# Netscale48HD_Antenna_Selector.net
KiCad netlist of a schematic drawn in Altium Designer
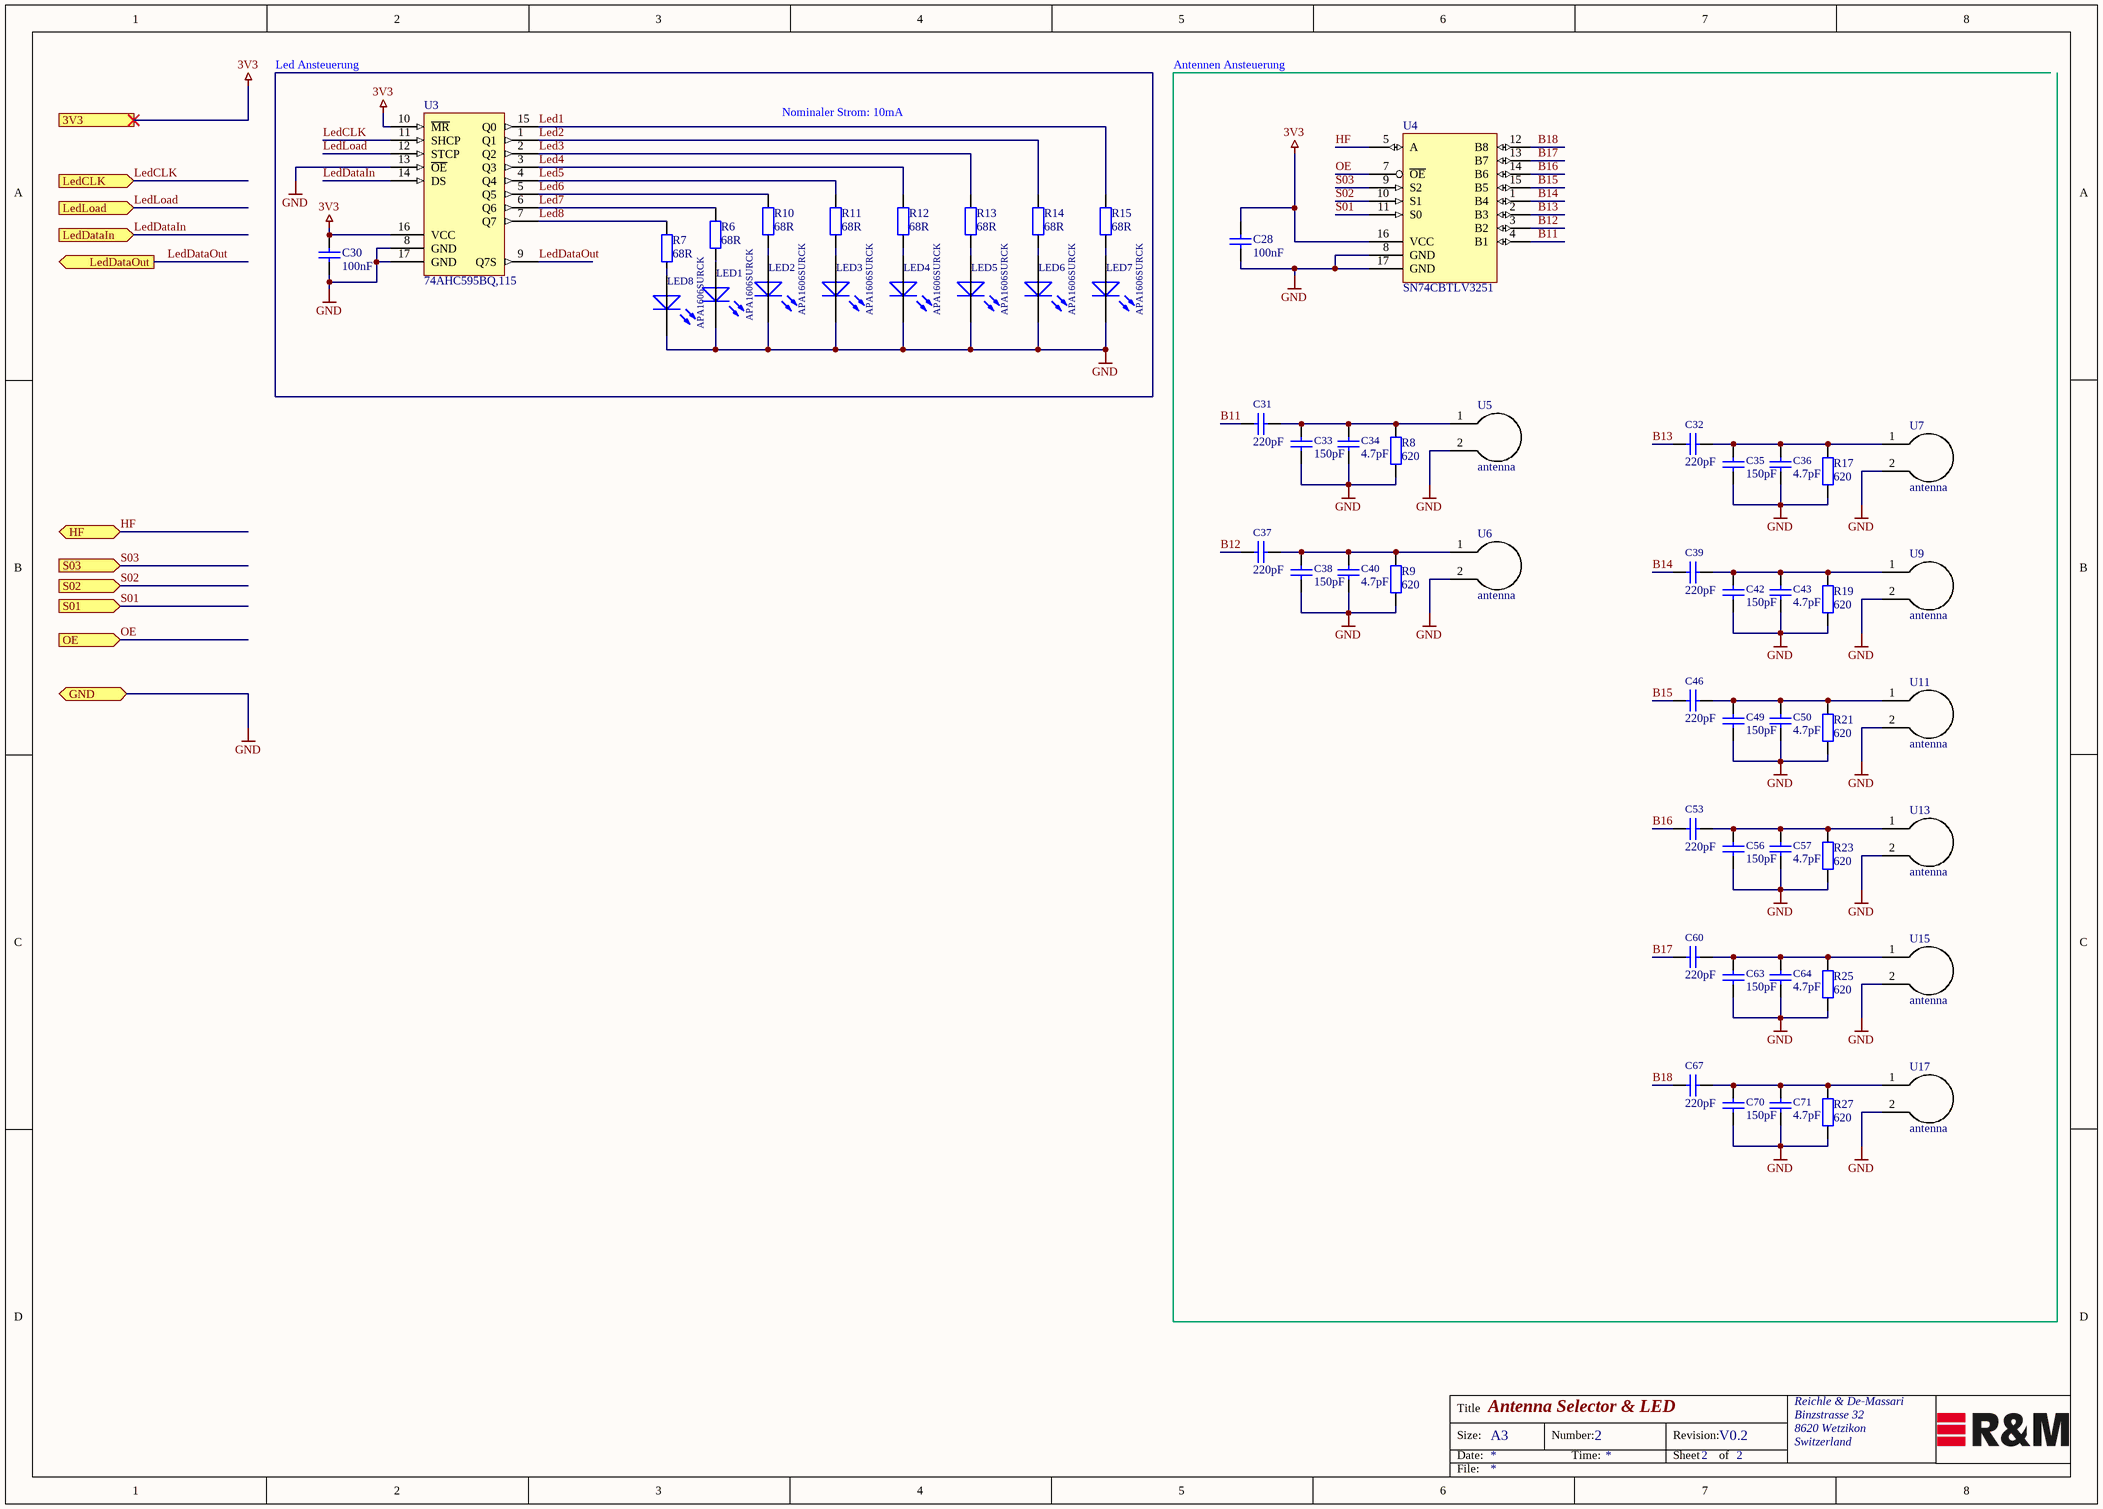
[diagram p0: Netscale48HD_Antenna_Selector.SchDoc]

(export (version "E")
  (design (tool "Eeschema 10.0.6"))
  (components
    (comp (ref "C28")
      (value "100nF")
      (footprint "CAPC1005X55N")
      (description "0.1µF ±10% 10V Ceramic Capacitor X5R 0402 (1005 Metric)")
      (fields (field (name "TOLERANCE") "Â±10%") (field (name "MANUFACTURER") "Taiyo Yuden"))
      (libsource (lib "altium-import") (part "root_1_CMP-1033-00660-1_"))
    )
    (comp (ref "C30")
      (value "100nF")
      (footprint "CAPC1005X55N")
      (description "0.1µF ±10% 10V Ceramic Capacitor X5R 0402 (1005 Metric)")
      (fields (field (name "TOLERANCE") "Â±10%") (field (name "MANUFACTURER") "Taiyo Yuden"))
      (libsource (lib "altium-import") (part "root_1_CMP-1033-00660-1_"))
    )
    (comp (ref "C31")
      (value "220pF")
      (footprint "CAPC1005X55N")
      (description "220pF ±1% 50V Ceramic Capacitor C0G, NP0 0402 (1005 Metric)")
      (fields
        (field (name "MANUFACTURER") "Murata Electronics")
        (field (name "Comment") "GCM1555C1H221FA16D")
      )
      (libsource (lib "NTB Vault") (part "706xx_R+M_InteliPhyII_KTI-00070-A.1"))
    )
    (comp (ref "C32")
      (value "220pF")
      (footprint "CAPC1005X55N")
      (description "220pF ±1% 50V Ceramic Capacitor C0G, NP0 0402 (1005 Metric)")
      (fields
        (field (name "MANUFACTURER") "Murata Electronics")
        (field (name "Comment") "GCM1555C1H221FA16D")
      )
      (libsource (lib "NTB Vault") (part "706xx_R+M_InteliPhyII_KTI-00070-A.1"))
    )
    (comp (ref "C33")
      (value "150pF")
      (footprint "CAPC1005X55N")
      (description "150pF ±1% 50V Ceramic Capacitor C0G, NP0 0402 (1005 Metric)")
      (fields
        (field (name "MANUFACTURER") "Murata Electronics North America")
        (field (name "Comment") "GRM1555C1H151FA01D")
      )
      (libsource (lib "NTB Vault") (part "706xx_R+M_InteliPhyII_KTI-00069-A.1"))
    )
    (comp (ref "C34")
      (value "4.7pF")
      (footprint "CAPC1005X55N")
      (description "4.7pF ±0.05pF 50V Ceramic Capacitor C0G, NP0 0402 (1005 Metric)")
      (fields
        (field (name "MANUFACTURER") "Murata Electronics North America")
        (field (name "Comment") "GJM1555C1H4R7WB01D")
      )
      (libsource (lib "NTB Vault") (part "706xx_R+M_InteliPhyII_KTI-00023-A.1"))
    )
    (comp (ref "C35")
      (value "150pF")
      (footprint "CAPC1005X55N")
      (description "150pF ±1% 50V Ceramic Capacitor C0G, NP0 0402 (1005 Metric)")
      (fields
        (field (name "MANUFACTURER") "Murata Electronics North America")
        (field (name "Comment") "GRM1555C1H151FA01D")
      )
      (libsource (lib "NTB Vault") (part "706xx_R+M_InteliPhyII_KTI-00069-A.1"))
    )
    (comp (ref "C36")
      (value "4.7pF")
      (footprint "CAPC1005X55N")
      (description "4.7pF ±0.05pF 50V Ceramic Capacitor C0G, NP0 0402 (1005 Metric)")
      (fields
        (field (name "MANUFACTURER") "Murata Electronics North America")
        (field (name "Comment") "GJM1555C1H4R7WB01D")
      )
      (libsource (lib "NTB Vault") (part "706xx_R+M_InteliPhyII_KTI-00023-A.1"))
    )
    (comp (ref "C37")
      (value "220pF")
      (footprint "CAPC1005X55N")
      (description "220pF ±1% 50V Ceramic Capacitor C0G, NP0 0402 (1005 Metric)")
      (fields
        (field (name "MANUFACTURER") "Murata Electronics")
        (field (name "Comment") "GCM1555C1H221FA16D")
      )
      (libsource (lib "NTB Vault") (part "706xx_R+M_InteliPhyII_KTI-00070-A.1"))
    )
    (comp (ref "C38")
      (value "150pF")
      (footprint "CAPC1005X55N")
      (description "150pF ±1% 50V Ceramic Capacitor C0G, NP0 0402 (1005 Metric)")
      (fields
        (field (name "MANUFACTURER") "Murata Electronics North America")
        (field (name "Comment") "GRM1555C1H151FA01D")
      )
      (libsource (lib "NTB Vault") (part "706xx_R+M_InteliPhyII_KTI-00069-A.1"))
    )
    (comp (ref "C39")
      (value "220pF")
      (footprint "CAPC1005X55N")
      (description "220pF ±1% 50V Ceramic Capacitor C0G, NP0 0402 (1005 Metric)")
      (fields
        (field (name "MANUFACTURER") "Murata Electronics")
        (field (name "Comment") "GCM1555C1H221FA16D")
      )
      (libsource (lib "NTB Vault") (part "706xx_R+M_InteliPhyII_KTI-00070-A.1"))
    )
    (comp (ref "C40")
      (value "4.7pF")
      (footprint "CAPC1005X55N")
      (description "4.7pF ±0.05pF 50V Ceramic Capacitor C0G, NP0 0402 (1005 Metric)")
      (fields
        (field (name "MANUFACTURER") "Murata Electronics North America")
        (field (name "Comment") "GJM1555C1H4R7WB01D")
      )
      (libsource (lib "NTB Vault") (part "706xx_R+M_InteliPhyII_KTI-00023-A.1"))
    )
    (comp (ref "C42")
      (value "150pF")
      (footprint "CAPC1005X55N")
      (description "150pF ±1% 50V Ceramic Capacitor C0G, NP0 0402 (1005 Metric)")
      (fields
        (field (name "MANUFACTURER") "Murata Electronics North America")
        (field (name "Comment") "GRM1555C1H151FA01D")
      )
      (libsource (lib "NTB Vault") (part "706xx_R+M_InteliPhyII_KTI-00069-A.1"))
    )
    (comp (ref "C43")
      (value "4.7pF")
      (footprint "CAPC1005X55N")
      (description "4.7pF ±0.05pF 50V Ceramic Capacitor C0G, NP0 0402 (1005 Metric)")
      (fields
        (field (name "MANUFACTURER") "Murata Electronics North America")
        (field (name "Comment") "GJM1555C1H4R7WB01D")
      )
      (libsource (lib "NTB Vault") (part "706xx_R+M_InteliPhyII_KTI-00023-A.1"))
    )
    (comp (ref "C46")
      (value "220pF")
      (footprint "CAPC1005X55N")
      (description "220pF ±1% 50V Ceramic Capacitor C0G, NP0 0402 (1005 Metric)")
      (fields
        (field (name "MANUFACTURER") "Murata Electronics")
        (field (name "Comment") "GCM1555C1H221FA16D")
      )
      (libsource (lib "NTB Vault") (part "706xx_R+M_InteliPhyII_KTI-00070-A.1"))
    )
    (comp (ref "C49")
      (value "150pF")
      (footprint "CAPC1005X55N")
      (description "150pF ±1% 50V Ceramic Capacitor C0G, NP0 0402 (1005 Metric)")
      (fields
        (field (name "MANUFACTURER") "Murata Electronics North America")
        (field (name "Comment") "GRM1555C1H151FA01D")
      )
      (libsource (lib "NTB Vault") (part "706xx_R+M_InteliPhyII_KTI-00069-A.1"))
    )
    (comp (ref "C50")
      (value "4.7pF")
      (footprint "CAPC1005X55N")
      (description "4.7pF ±0.05pF 50V Ceramic Capacitor C0G, NP0 0402 (1005 Metric)")
      (fields
        (field (name "MANUFACTURER") "Murata Electronics North America")
        (field (name "Comment") "GJM1555C1H4R7WB01D")
      )
      (libsource (lib "NTB Vault") (part "706xx_R+M_InteliPhyII_KTI-00023-A.1"))
    )
    (comp (ref "C53")
      (value "220pF")
      (footprint "CAPC1005X55N")
      (description "220pF ±1% 50V Ceramic Capacitor C0G, NP0 0402 (1005 Metric)")
      (fields
        (field (name "MANUFACTURER") "Murata Electronics")
        (field (name "Comment") "GCM1555C1H221FA16D")
      )
      (libsource (lib "NTB Vault") (part "706xx_R+M_InteliPhyII_KTI-00070-A.1"))
    )
    (comp (ref "C56")
      (value "150pF")
      (footprint "CAPC1005X55N")
      (description "150pF ±1% 50V Ceramic Capacitor C0G, NP0 0402 (1005 Metric)")
      (fields
        (field (name "MANUFACTURER") "Murata Electronics North America")
        (field (name "Comment") "GRM1555C1H151FA01D")
      )
      (libsource (lib "NTB Vault") (part "706xx_R+M_InteliPhyII_KTI-00069-A.1"))
    )
    (comp (ref "C57")
      (value "4.7pF")
      (footprint "CAPC1005X55N")
      (description "4.7pF ±0.05pF 50V Ceramic Capacitor C0G, NP0 0402 (1005 Metric)")
      (fields
        (field (name "MANUFACTURER") "Murata Electronics North America")
        (field (name "Comment") "GJM1555C1H4R7WB01D")
      )
      (libsource (lib "NTB Vault") (part "706xx_R+M_InteliPhyII_KTI-00023-A.1"))
    )
    (comp (ref "C60")
      (value "220pF")
      (footprint "CAPC1005X55N")
      (description "220pF ±1% 50V Ceramic Capacitor C0G, NP0 0402 (1005 Metric)")
      (fields
        (field (name "MANUFACTURER") "Murata Electronics")
        (field (name "Comment") "GCM1555C1H221FA16D")
      )
      (libsource (lib "NTB Vault") (part "706xx_R+M_InteliPhyII_KTI-00070-A.1"))
    )
    (comp (ref "C63")
      (value "150pF")
      (footprint "CAPC1005X55N")
      (description "150pF ±1% 50V Ceramic Capacitor C0G, NP0 0402 (1005 Metric)")
      (fields
        (field (name "MANUFACTURER") "Murata Electronics North America")
        (field (name "Comment") "GRM1555C1H151FA01D")
      )
      (libsource (lib "NTB Vault") (part "706xx_R+M_InteliPhyII_KTI-00069-A.1"))
    )
    (comp (ref "C64")
      (value "4.7pF")
      (footprint "CAPC1005X55N")
      (description "4.7pF ±0.05pF 50V Ceramic Capacitor C0G, NP0 0402 (1005 Metric)")
      (fields
        (field (name "MANUFACTURER") "Murata Electronics North America")
        (field (name "Comment") "GJM1555C1H4R7WB01D")
      )
      (libsource (lib "NTB Vault") (part "706xx_R+M_InteliPhyII_KTI-00023-A.1"))
    )
    (comp (ref "C67")
      (value "220pF")
      (footprint "CAPC1005X55N")
      (description "220pF ±1% 50V Ceramic Capacitor C0G, NP0 0402 (1005 Metric)")
      (fields
        (field (name "MANUFACTURER") "Murata Electronics")
        (field (name "Comment") "GCM1555C1H221FA16D")
      )
      (libsource (lib "NTB Vault") (part "706xx_R+M_InteliPhyII_KTI-00070-A.1"))
    )
    (comp (ref "C70")
      (value "150pF")
      (footprint "CAPC1005X55N")
      (description "150pF ±1% 50V Ceramic Capacitor C0G, NP0 0402 (1005 Metric)")
      (fields
        (field (name "MANUFACTURER") "Murata Electronics North America")
        (field (name "Comment") "GRM1555C1H151FA01D")
      )
      (libsource (lib "NTB Vault") (part "706xx_R+M_InteliPhyII_KTI-00069-A.1"))
    )
    (comp (ref "C71")
      (value "4.7pF")
      (footprint "CAPC1005X55N")
      (description "4.7pF ±0.05pF 50V Ceramic Capacitor C0G, NP0 0402 (1005 Metric)")
      (fields
        (field (name "MANUFACTURER") "Murata Electronics North America")
        (field (name "Comment") "GJM1555C1H4R7WB01D")
      )
      (libsource (lib "NTB Vault") (part "706xx_R+M_InteliPhyII_KTI-00023-A.1"))
    )
    (comp (ref "LED1")
      (value "APA1606SURCK")
      (footprint "Kingbright_SMD_2_RWH")
      (description "Red 630nm LED Indication - Discrete 1.95V 2-SMD, No Lead")
      (fields (field (name "MANUFACTURER") "Kingbright"))
      (libsource (lib "altium-import") (part "root_1_LED_K1_A2_"))
    )
    (comp (ref "LED2")
      (value "APA1606SURCK")
      (footprint "Kingbright_SMD_2_RWH")
      (description "Red 630nm LED Indication - Discrete 1.95V 2-SMD, No Lead")
      (fields (field (name "MANUFACTURER") "Kingbright"))
      (libsource (lib "altium-import") (part "root_1_LED_K1_A2_"))
    )
    (comp (ref "LED3")
      (value "APA1606SURCK")
      (footprint "Kingbright_SMD_2_RWH")
      (description "Red 630nm LED Indication - Discrete 1.95V 2-SMD, No Lead")
      (fields (field (name "MANUFACTURER") "Kingbright"))
      (libsource (lib "altium-import") (part "root_1_LED_K1_A2_"))
    )
    (comp (ref "LED4")
      (value "APA1606SURCK")
      (footprint "Kingbright_SMD_2_RWH")
      (description "Red 630nm LED Indication - Discrete 1.95V 2-SMD, No Lead")
      (fields (field (name "MANUFACTURER") "Kingbright"))
      (libsource (lib "altium-import") (part "root_1_LED_K1_A2_"))
    )
    (comp (ref "LED5")
      (value "APA1606SURCK")
      (footprint "Kingbright_SMD_2_RWH")
      (description "Red 630nm LED Indication - Discrete 1.95V 2-SMD, No Lead")
      (fields (field (name "MANUFACTURER") "Kingbright"))
      (libsource (lib "altium-import") (part "root_1_LED_K1_A2_"))
    )
    (comp (ref "LED6")
      (value "APA1606SURCK")
      (footprint "Kingbright_SMD_2_RWH")
      (description "Red 630nm LED Indication - Discrete 1.95V 2-SMD, No Lead")
      (fields (field (name "MANUFACTURER") "Kingbright"))
      (libsource (lib "altium-import") (part "root_1_LED_K1_A2_"))
    )
    (comp (ref "LED7")
      (value "APA1606SURCK")
      (footprint "Kingbright_SMD_2_RWH")
      (description "Red 630nm LED Indication - Discrete 1.95V 2-SMD, No Lead")
      (fields (field (name "MANUFACTURER") "Kingbright"))
      (libsource (lib "altium-import") (part "root_1_LED_K1_A2_"))
    )
    (comp (ref "LED8")
      (value "APA1606SURCK")
      (footprint "Kingbright_SMD_2_RWH")
      (description "Red 630nm LED Indication - Discrete 1.95V 2-SMD, No Lead")
      (fields (field (name "MANUFACTURER") "Kingbright"))
      (libsource (lib "altium-import") (part "root_1_LED_K1_A2_"))
    )
    (comp (ref "R6")
      (value "68R")
      (footprint "RESC1005X40N")
      (description "68 Ohms ±1% 0.125W, 1/8W Chip Resistor 0402 (1005 Metric) Pulse Withstanding Thick Film")
      (fields
        (field (name "MANUFACTURER") "TE Connectivity Passive Product")
        (field (name "Comment") "CRGP0402F68R")
      )
      (libsource (lib "RDM_Altium_Library") (part "PassResBas0201-00055-A.2"))
    )
    (comp (ref "R7")
      (value "68R")
      (footprint "RESC1005X40N")
      (description "68 Ohms ±1% 0.125W, 1/8W Chip Resistor 0402 (1005 Metric) Pulse Withstanding Thick Film")
      (fields
        (field (name "MANUFACTURER") "TE Connectivity Passive Product")
        (field (name "Comment") "CRGP0402F68R")
      )
      (libsource (lib "RDM_Altium_Library") (part "PassResBas0201-00055-A.2"))
    )
    (comp (ref "R8")
      (value "620")
      (footprint "RESC1005X40N")
      (description "620 Ohms ±1% 0.1W, 1/10W Chip Resistor 0402 (1005 Metric) Automotive AEC-Q200 Thick Film")
      (fields
        (field (name "MANUFACTURER") "Panasonic Electronic Components")
        (field (name "Comment") "ERJ-2RKF6200X")
      )
      (libsource (lib "") (part "PassResBas0201-00055-A.2_1"))
    )
    (comp (ref "R9")
      (value "620")
      (footprint "RESC1005X40N")
      (description "620 Ohms ±1% 0.1W, 1/10W Chip Resistor 0402 (1005 Metric) Automotive AEC-Q200 Thick Film")
      (fields
        (field (name "MANUFACTURER") "Panasonic Electronic Components")
        (field (name "Comment") "ERJ-2RKF6200X")
      )
      (libsource (lib "") (part "PassResBas0201-00055-A.2_1"))
    )
    (comp (ref "R10")
      (value "68R")
      (footprint "RESC1005X40N")
      (description "68 Ohms ±1% 0.125W, 1/8W Chip Resistor 0402 (1005 Metric) Pulse Withstanding Thick Film")
      (fields
        (field (name "MANUFACTURER") "TE Connectivity Passive Product")
        (field (name "Comment") "CRGP0402F68R")
      )
      (libsource (lib "RDM_Altium_Library") (part "PassResBas0201-00055-A.2"))
    )
    (comp (ref "R11")
      (value "68R")
      (footprint "RESC1005X40N")
      (description "68 Ohms ±1% 0.125W, 1/8W Chip Resistor 0402 (1005 Metric) Pulse Withstanding Thick Film")
      (fields
        (field (name "MANUFACTURER") "TE Connectivity Passive Product")
        (field (name "Comment") "CRGP0402F68R")
      )
      (libsource (lib "RDM_Altium_Library") (part "PassResBas0201-00055-A.2"))
    )
    (comp (ref "R12")
      (value "68R")
      (footprint "RESC1005X40N")
      (description "68 Ohms ±1% 0.125W, 1/8W Chip Resistor 0402 (1005 Metric) Pulse Withstanding Thick Film")
      (fields
        (field (name "MANUFACTURER") "TE Connectivity Passive Product")
        (field (name "Comment") "CRGP0402F68R")
      )
      (libsource (lib "RDM_Altium_Library") (part "PassResBas0201-00055-A.2"))
    )
    (comp (ref "R13")
      (value "68R")
      (footprint "RESC1005X40N")
      (description "68 Ohms ±1% 0.125W, 1/8W Chip Resistor 0402 (1005 Metric) Pulse Withstanding Thick Film")
      (fields
        (field (name "MANUFACTURER") "TE Connectivity Passive Product")
        (field (name "Comment") "CRGP0402F68R")
      )
      (libsource (lib "RDM_Altium_Library") (part "PassResBas0201-00055-A.2"))
    )
    (comp (ref "R14")
      (value "68R")
      (footprint "RESC1005X40N")
      (description "68 Ohms ±1% 0.125W, 1/8W Chip Resistor 0402 (1005 Metric) Pulse Withstanding Thick Film")
      (fields
        (field (name "MANUFACTURER") "TE Connectivity Passive Product")
        (field (name "Comment") "CRGP0402F68R")
      )
      (libsource (lib "RDM_Altium_Library") (part "PassResBas0201-00055-A.2"))
    )
    (comp (ref "R15")
      (value "68R")
      (footprint "RESC1005X40N")
      (description "68 Ohms ±1% 0.125W, 1/8W Chip Resistor 0402 (1005 Metric) Pulse Withstanding Thick Film")
      (fields
        (field (name "MANUFACTURER") "TE Connectivity Passive Product")
        (field (name "Comment") "CRGP0402F68R")
      )
      (libsource (lib "RDM_Altium_Library") (part "PassResBas0201-00055-A.2"))
    )
    (comp (ref "R17")
      (value "620")
      (footprint "RESC1005X40N")
      (description "620 Ohms ±1% 0.1W, 1/10W Chip Resistor 0402 (1005 Metric) Automotive AEC-Q200 Thick Film")
      (fields
        (field (name "MANUFACTURER") "Panasonic Electronic Components")
        (field (name "Comment") "ERJ-2RKF6200X")
      )
      (libsource (lib "") (part "PassResBas0201-00055-A.2_1"))
    )
    (comp (ref "R19")
      (value "620")
      (footprint "RESC1005X40N")
      (description "620 Ohms ±1% 0.1W, 1/10W Chip Resistor 0402 (1005 Metric) Automotive AEC-Q200 Thick Film")
      (fields
        (field (name "MANUFACTURER") "Panasonic Electronic Components")
        (field (name "Comment") "ERJ-2RKF6200X")
      )
      (libsource (lib "") (part "PassResBas0201-00055-A.2_1"))
    )
    (comp (ref "R21")
      (value "620")
      (footprint "RESC1005X40N")
      (description "620 Ohms ±1% 0.1W, 1/10W Chip Resistor 0402 (1005 Metric) Automotive AEC-Q200 Thick Film")
      (fields
        (field (name "MANUFACTURER") "Panasonic Electronic Components")
        (field (name "Comment") "ERJ-2RKF6200X")
      )
      (libsource (lib "") (part "PassResBas0201-00055-A.2_1"))
    )
    (comp (ref "R23")
      (value "620")
      (footprint "RESC1005X40N")
      (description "620 Ohms ±1% 0.1W, 1/10W Chip Resistor 0402 (1005 Metric) Automotive AEC-Q200 Thick Film")
      (fields
        (field (name "MANUFACTURER") "Panasonic Electronic Components")
        (field (name "Comment") "ERJ-2RKF6200X")
      )
      (libsource (lib "") (part "PassResBas0201-00055-A.2_1"))
    )
    (comp (ref "R25")
      (value "620")
      (footprint "RESC1005X40N")
      (description "620 Ohms ±1% 0.1W, 1/10W Chip Resistor 0402 (1005 Metric) Automotive AEC-Q200 Thick Film")
      (fields
        (field (name "MANUFACTURER") "Panasonic Electronic Components")
        (field (name "Comment") "ERJ-2RKF6200X")
      )
      (libsource (lib "") (part "PassResBas0201-00055-A.2_1"))
    )
    (comp (ref "R27")
      (value "620")
      (footprint "RESC1005X40N")
      (description "620 Ohms ±1% 0.1W, 1/10W Chip Resistor 0402 (1005 Metric) Automotive AEC-Q200 Thick Film")
      (fields
        (field (name "MANUFACTURER") "Panasonic Electronic Components")
        (field (name "Comment") "ERJ-2RKF6200X")
      )
      (libsource (lib "") (part "PassResBas0201-00055-A.2_1"))
    )
    (comp (ref "U3")
      (value "74AHC595BQ,115")
      (footprint "NexperiaUSAInc_16-VFQFN_16_R")
      (description "IC 8BIT SHIFT REGISTER 16HVQFN")
      (fields (field (name "MANUFACTURER") "Nexperia USA Inc."))
      (libsource (lib "RDM_Altium_Library") (part "NexperiaUSAInc_74AHC595,115_16-VFQFN_16"))
    )
    (comp (ref "U4")
      (value "SN74CBTLV3251")
      (footprint "TexasInstruments_16-VFQFN_16_R")
      (description "Multiplexer Switch ICs Sngl-Pole Dbl-Throw Analog Switch")
      (fields (field (name "MANUFACTURER") "Texas Instruments"))
      (libsource (lib "RDM_Altium_Library") (part "SN74CBTLV3251RGYR"))
    )
    (comp (ref "U5")
      (value "antenna")
      (footprint "antenna_1_layer")
      (libsource (lib "RDM_Altium_Library") (part "antenna"))
    )
    (comp (ref "U6")
      (value "antenna")
      (footprint "antenna_1_layer")
      (libsource (lib "RDM_Altium_Library") (part "antenna"))
    )
    (comp (ref "U7")
      (value "antenna")
      (footprint "antenna_1_layer")
      (libsource (lib "RDM_Altium_Library") (part "antenna"))
    )
    (comp (ref "U9")
      (value "antenna")
      (footprint "antenna_1_layer")
      (libsource (lib "RDM_Altium_Library") (part "antenna"))
    )
    (comp (ref "U11")
      (value "antenna")
      (footprint "antenna_1_layer")
      (libsource (lib "RDM_Altium_Library") (part "antenna"))
    )
    (comp (ref "U13")
      (value "antenna")
      (footprint "antenna_1_layer")
      (libsource (lib "RDM_Altium_Library") (part "antenna"))
    )
    (comp (ref "U15")
      (value "antenna")
      (footprint "antenna_1_layer")
      (libsource (lib "RDM_Altium_Library") (part "antenna"))
    )
    (comp (ref "U17")
      (value "antenna")
      (footprint "antenna_1_layer")
      (libsource (lib "RDM_Altium_Library") (part "antenna"))
    )
  )
  (nets
    (net (code "1") (name "/B11") (class "Default")
      (node (ref "C31") (pin "1") (pinfunction "Pos_1") (pintype "passive"))
      (node (ref "U4") (pin "4") (pinfunction "B1_4") (pintype "bidirectional"))
    )
    (net (code "2") (name "/B12") (class "Default")
      (node (ref "C37") (pin "1") (pinfunction "Pos_1") (pintype "passive"))
      (node (ref "U4") (pin "3") (pinfunction "B2_3") (pintype "bidirectional"))
    )
    (net (code "3") (name "/B13") (class "Default")
      (node (ref "C32") (pin "1") (pinfunction "Pos_1") (pintype "passive"))
      (node (ref "U4") (pin "2") (pinfunction "B3_2") (pintype "bidirectional"))
    )
    (net (code "4") (name "/B14") (class "Default")
      (node (ref "C39") (pin "1") (pinfunction "Pos_1") (pintype "passive"))
      (node (ref "U4") (pin "1") (pinfunction "B4_1") (pintype "bidirectional"))
    )
    (net (code "5") (name "/B15") (class "Default")
      (node (ref "C46") (pin "1") (pinfunction "Pos_1") (pintype "passive"))
      (node (ref "U4") (pin "15") (pinfunction "B5_15") (pintype "bidirectional"))
    )
    (net (code "6") (name "/B16") (class "Default")
      (node (ref "C53") (pin "1") (pinfunction "Pos_1") (pintype "passive"))
      (node (ref "U4") (pin "14") (pinfunction "B6_14") (pintype "bidirectional"))
    )
    (net (code "7") (name "/B17") (class "Default")
      (node (ref "C60") (pin "1") (pinfunction "Pos_1") (pintype "passive"))
      (node (ref "U4") (pin "13") (pinfunction "B7_13") (pintype "bidirectional"))
    )
    (net (code "8") (name "/B18") (class "Default")
      (node (ref "C67") (pin "1") (pinfunction "Pos_1") (pintype "passive"))
      (node (ref "U4") (pin "12") (pinfunction "B8_12") (pintype "bidirectional"))
    )
    (net (code "9") (name "/HF") (class "Default")
      (node (ref "U4") (pin "5") (pinfunction "A_5") (pintype "bidirectional"))
    )
    (net (code "10") (name "/Led1") (class "Default")
      (node (ref "R15") (pin "1") (pinfunction "1_1") (pintype "passive"))
      (node (ref "U3") (pin "15") (pinfunction "Q0_15") (pintype "output"))
    )
    (net (code "11") (name "/Led2") (class "Default")
      (node (ref "R14") (pin "1") (pinfunction "1_1") (pintype "passive"))
      (node (ref "U3") (pin "1") (pinfunction "Q1_1") (pintype "output"))
    )
    (net (code "12") (name "/Led3") (class "Default")
      (node (ref "R13") (pin "1") (pinfunction "1_1") (pintype "passive"))
      (node (ref "U3") (pin "2") (pinfunction "Q2_2") (pintype "output"))
    )
    (net (code "13") (name "/Led4") (class "Default")
      (node (ref "R12") (pin "1") (pinfunction "1_1") (pintype "passive"))
      (node (ref "U3") (pin "3") (pinfunction "Q3_3") (pintype "output"))
    )
    (net (code "14") (name "/Led5") (class "Default")
      (node (ref "R11") (pin "1") (pinfunction "1_1") (pintype "passive"))
      (node (ref "U3") (pin "4") (pinfunction "Q4_4") (pintype "output"))
    )
    (net (code "15") (name "/Led6") (class "Default")
      (node (ref "R10") (pin "1") (pinfunction "1_1") (pintype "passive"))
      (node (ref "U3") (pin "5") (pinfunction "Q5_5") (pintype "output"))
    )
    (net (code "16") (name "/Led7") (class "Default")
      (node (ref "R6") (pin "1") (pinfunction "1_1") (pintype "passive"))
      (node (ref "U3") (pin "6") (pinfunction "Q6_6") (pintype "output"))
    )
    (net (code "17") (name "/Led8") (class "Default")
      (node (ref "R7") (pin "1") (pinfunction "1_1") (pintype "passive"))
      (node (ref "U3") (pin "7") (pinfunction "Q7_7") (pintype "output"))
    )
    (net (code "18") (name "/LedCLK") (class "Default")
      (node (ref "U3") (pin "11") (pinfunction "SHCP_11") (pintype "input"))
    )
    (net (code "19") (name "/LedDataIn") (class "Default")
      (node (ref "U3") (pin "14") (pinfunction "DS_14") (pintype "input"))
    )
    (net (code "20") (name "/LedDataOut") (class "Default")
      (node (ref "U3") (pin "9") (pinfunction "Q7S_9") (pintype "output"))
    )
    (net (code "21") (name "/LedLoad") (class "Default")
      (node (ref "U3") (pin "12") (pinfunction "STCP_12") (pintype "input"))
    )
    (net (code "22") (name "/OE") (class "Default")
      (node (ref "U4") (pin "7") (pinfunction "~{OE}_7") (pintype "passive"))
    )
    (net (code "23") (name "/S01") (class "Default")
      (node (ref "U4") (pin "11") (pinfunction "S0_11") (pintype "input"))
    )
    (net (code "24") (name "/S02") (class "Default")
      (node (ref "U4") (pin "10") (pinfunction "S1_10") (pintype "input"))
    )
    (net (code "25") (name "/S03") (class "Default")
      (node (ref "U4") (pin "9") (pinfunction "S2_9") (pintype "input"))
    )
    (net (code "26") (name "3V3") (class "Default")
      (node (ref "C28") (pin "2") (pinfunction "2_2") (pintype "passive"))
      (node (ref "C30") (pin "2") (pinfunction "2_2") (pintype "passive"))
      (node (ref "U3") (pin "10") (pinfunction "~{MR}_10") (pintype "input"))
      (node (ref "U3") (pin "16") (pinfunction "VCC_16") (pintype "power_in"))
      (node (ref "U4") (pin "16") (pinfunction "VCC_16") (pintype "power_in"))
    )
    (net (code "27") (name "GND") (class "Default")
      (node (ref "C28") (pin "1") (pinfunction "1_1") (pintype "passive"))
      (node (ref "C30") (pin "1") (pinfunction "1_1") (pintype "passive"))
      (node (ref "C33") (pin "1") (pinfunction "Pos_1") (pintype "passive"))
      (node (ref "C34") (pin "1") (pinfunction "Pos_1") (pintype "passive"))
      (node (ref "C35") (pin "1") (pinfunction "Pos_1") (pintype "passive"))
      (node (ref "C36") (pin "1") (pinfunction "Pos_1") (pintype "passive"))
      (node (ref "C38") (pin "1") (pinfunction "Pos_1") (pintype "passive"))
      (node (ref "C40") (pin "1") (pinfunction "Pos_1") (pintype "passive"))
      (node (ref "C42") (pin "1") (pinfunction "Pos_1") (pintype "passive"))
      (node (ref "C43") (pin "1") (pinfunction "Pos_1") (pintype "passive"))
      (node (ref "C49") (pin "1") (pinfunction "Pos_1") (pintype "passive"))
      (node (ref "C50") (pin "1") (pinfunction "Pos_1") (pintype "passive"))
      (node (ref "C56") (pin "1") (pinfunction "Pos_1") (pintype "passive"))
      (node (ref "C57") (pin "1") (pinfunction "Pos_1") (pintype "passive"))
      (node (ref "C63") (pin "1") (pinfunction "Pos_1") (pintype "passive"))
      (node (ref "C64") (pin "1") (pinfunction "Pos_1") (pintype "passive"))
      (node (ref "C70") (pin "1") (pinfunction "Pos_1") (pintype "passive"))
      (node (ref "C71") (pin "1") (pinfunction "Pos_1") (pintype "passive"))
      (node (ref "LED1") (pin "1") (pinfunction "K_1") (pintype "passive"))
      (node (ref "LED2") (pin "1") (pinfunction "K_1") (pintype "passive"))
      (node (ref "LED3") (pin "1") (pinfunction "K_1") (pintype "passive"))
      (node (ref "LED4") (pin "1") (pinfunction "K_1") (pintype "passive"))
      (node (ref "LED5") (pin "1") (pinfunction "K_1") (pintype "passive"))
      (node (ref "LED6") (pin "1") (pinfunction "K_1") (pintype "passive"))
      (node (ref "LED7") (pin "1") (pinfunction "K_1") (pintype "passive"))
      (node (ref "LED8") (pin "1") (pinfunction "K_1") (pintype "passive"))
      (node (ref "R17") (pin "1") (pinfunction "1_1") (pintype "passive"))
      (node (ref "R19") (pin "1") (pinfunction "1_1") (pintype "passive"))
      (node (ref "R21") (pin "1") (pinfunction "1_1") (pintype "passive"))
      (node (ref "R23") (pin "1") (pinfunction "1_1") (pintype "passive"))
      (node (ref "R25") (pin "1") (pinfunction "1_1") (pintype "passive"))
      (node (ref "R27") (pin "1") (pinfunction "1_1") (pintype "passive"))
      (node (ref "R8") (pin "1") (pinfunction "1_1") (pintype "passive"))
      (node (ref "R9") (pin "1") (pinfunction "1_1") (pintype "passive"))
      (node (ref "U11") (pin "2") (pinfunction "2_2") (pintype "passive"))
      (node (ref "U13") (pin "2") (pinfunction "2_2") (pintype "passive"))
      (node (ref "U15") (pin "2") (pinfunction "2_2") (pintype "passive"))
      (node (ref "U17") (pin "2") (pinfunction "2_2") (pintype "passive"))
      (node (ref "U3") (pin "13") (pinfunction "~{OE}_13") (pintype "input"))
      (node (ref "U3") (pin "17") (pinfunction "GND_17") (pintype "passive"))
      (node (ref "U3") (pin "8") (pinfunction "GND_8") (pintype "passive"))
      (node (ref "U4") (pin "17") (pinfunction "GND_17") (pintype "passive"))
      (node (ref "U4") (pin "8") (pinfunction "GND_8") (pintype "passive"))
      (node (ref "U5") (pin "2") (pinfunction "2_2") (pintype "passive"))
      (node (ref "U6") (pin "2") (pinfunction "2_2") (pintype "passive"))
      (node (ref "U7") (pin "2") (pinfunction "2_2") (pintype "passive"))
      (node (ref "U9") (pin "2") (pinfunction "2_2") (pintype "passive"))
    )
    (net (code "28") (name "Net-(C31-Neg)") (class "Default")
      (node (ref "C31") (pin "2") (pinfunction "Neg_2") (pintype "passive"))
      (node (ref "C33") (pin "2") (pinfunction "Neg_2") (pintype "passive"))
      (node (ref "C34") (pin "2") (pinfunction "Neg_2") (pintype "passive"))
      (node (ref "R8") (pin "2") (pinfunction "2_2") (pintype "passive"))
      (node (ref "U5") (pin "1") (pinfunction "1_1") (pintype "passive"))
    )
    (net (code "29") (name "Net-(C32-Neg)") (class "Default")
      (node (ref "C32") (pin "2") (pinfunction "Neg_2") (pintype "passive"))
      (node (ref "C35") (pin "2") (pinfunction "Neg_2") (pintype "passive"))
      (node (ref "C36") (pin "2") (pinfunction "Neg_2") (pintype "passive"))
      (node (ref "R17") (pin "2") (pinfunction "2_2") (pintype "passive"))
      (node (ref "U7") (pin "1") (pinfunction "1_1") (pintype "passive"))
    )
    (net (code "30") (name "Net-(C37-Neg)") (class "Default")
      (node (ref "C37") (pin "2") (pinfunction "Neg_2") (pintype "passive"))
      (node (ref "C38") (pin "2") (pinfunction "Neg_2") (pintype "passive"))
      (node (ref "C40") (pin "2") (pinfunction "Neg_2") (pintype "passive"))
      (node (ref "R9") (pin "2") (pinfunction "2_2") (pintype "passive"))
      (node (ref "U6") (pin "1") (pinfunction "1_1") (pintype "passive"))
    )
    (net (code "31") (name "Net-(C39-Neg)") (class "Default")
      (node (ref "C39") (pin "2") (pinfunction "Neg_2") (pintype "passive"))
      (node (ref "C42") (pin "2") (pinfunction "Neg_2") (pintype "passive"))
      (node (ref "C43") (pin "2") (pinfunction "Neg_2") (pintype "passive"))
      (node (ref "R19") (pin "2") (pinfunction "2_2") (pintype "passive"))
      (node (ref "U9") (pin "1") (pinfunction "1_1") (pintype "passive"))
    )
    (net (code "32") (name "Net-(C46-Neg)") (class "Default")
      (node (ref "C46") (pin "2") (pinfunction "Neg_2") (pintype "passive"))
      (node (ref "C49") (pin "2") (pinfunction "Neg_2") (pintype "passive"))
      (node (ref "C50") (pin "2") (pinfunction "Neg_2") (pintype "passive"))
      (node (ref "R21") (pin "2") (pinfunction "2_2") (pintype "passive"))
      (node (ref "U11") (pin "1") (pinfunction "1_1") (pintype "passive"))
    )
    (net (code "33") (name "Net-(C53-Neg)") (class "Default")
      (node (ref "C53") (pin "2") (pinfunction "Neg_2") (pintype "passive"))
      (node (ref "C56") (pin "2") (pinfunction "Neg_2") (pintype "passive"))
      (node (ref "C57") (pin "2") (pinfunction "Neg_2") (pintype "passive"))
      (node (ref "R23") (pin "2") (pinfunction "2_2") (pintype "passive"))
      (node (ref "U13") (pin "1") (pinfunction "1_1") (pintype "passive"))
    )
    (net (code "34") (name "Net-(C60-Neg)") (class "Default")
      (node (ref "C60") (pin "2") (pinfunction "Neg_2") (pintype "passive"))
      (node (ref "C63") (pin "2") (pinfunction "Neg_2") (pintype "passive"))
      (node (ref "C64") (pin "2") (pinfunction "Neg_2") (pintype "passive"))
      (node (ref "R25") (pin "2") (pinfunction "2_2") (pintype "passive"))
      (node (ref "U15") (pin "1") (pinfunction "1_1") (pintype "passive"))
    )
    (net (code "35") (name "Net-(C67-Neg)") (class "Default")
      (node (ref "C67") (pin "2") (pinfunction "Neg_2") (pintype "passive"))
      (node (ref "C70") (pin "2") (pinfunction "Neg_2") (pintype "passive"))
      (node (ref "C71") (pin "2") (pinfunction "Neg_2") (pintype "passive"))
      (node (ref "R27") (pin "2") (pinfunction "2_2") (pintype "passive"))
      (node (ref "U17") (pin "1") (pinfunction "1_1") (pintype "passive"))
    )
    (net (code "36") (name "Net-(LED1-A)") (class "Default")
      (node (ref "LED1") (pin "2") (pinfunction "A_2") (pintype "passive"))
      (node (ref "R6") (pin "2") (pinfunction "2_2") (pintype "passive"))
    )
    (net (code "37") (name "Net-(LED2-A)") (class "Default")
      (node (ref "LED2") (pin "2") (pinfunction "A_2") (pintype "passive"))
      (node (ref "R10") (pin "2") (pinfunction "2_2") (pintype "passive"))
    )
    (net (code "38") (name "Net-(LED3-A)") (class "Default")
      (node (ref "LED3") (pin "2") (pinfunction "A_2") (pintype "passive"))
      (node (ref "R11") (pin "2") (pinfunction "2_2") (pintype "passive"))
    )
    (net (code "39") (name "Net-(LED4-A)") (class "Default")
      (node (ref "LED4") (pin "2") (pinfunction "A_2") (pintype "passive"))
      (node (ref "R12") (pin "2") (pinfunction "2_2") (pintype "passive"))
    )
    (net (code "40") (name "Net-(LED5-A)") (class "Default")
      (node (ref "LED5") (pin "2") (pinfunction "A_2") (pintype "passive"))
      (node (ref "R13") (pin "2") (pinfunction "2_2") (pintype "passive"))
    )
    (net (code "41") (name "Net-(LED6-A)") (class "Default")
      (node (ref "LED6") (pin "2") (pinfunction "A_2") (pintype "passive"))
      (node (ref "R14") (pin "2") (pinfunction "2_2") (pintype "passive"))
    )
    (net (code "42") (name "Net-(LED7-A)") (class "Default")
      (node (ref "LED7") (pin "2") (pinfunction "A_2") (pintype "passive"))
      (node (ref "R15") (pin "2") (pinfunction "2_2") (pintype "passive"))
    )
    (net (code "43") (name "Net-(LED8-A)") (class "Default")
      (node (ref "LED8") (pin "2") (pinfunction "A_2") (pintype "passive"))
      (node (ref "R7") (pin "2") (pinfunction "2_2") (pintype "passive"))
    )
  )
)
